# intel-edison-pin-breakout.net
KiCad netlist of a schematic drawn in EAGLE
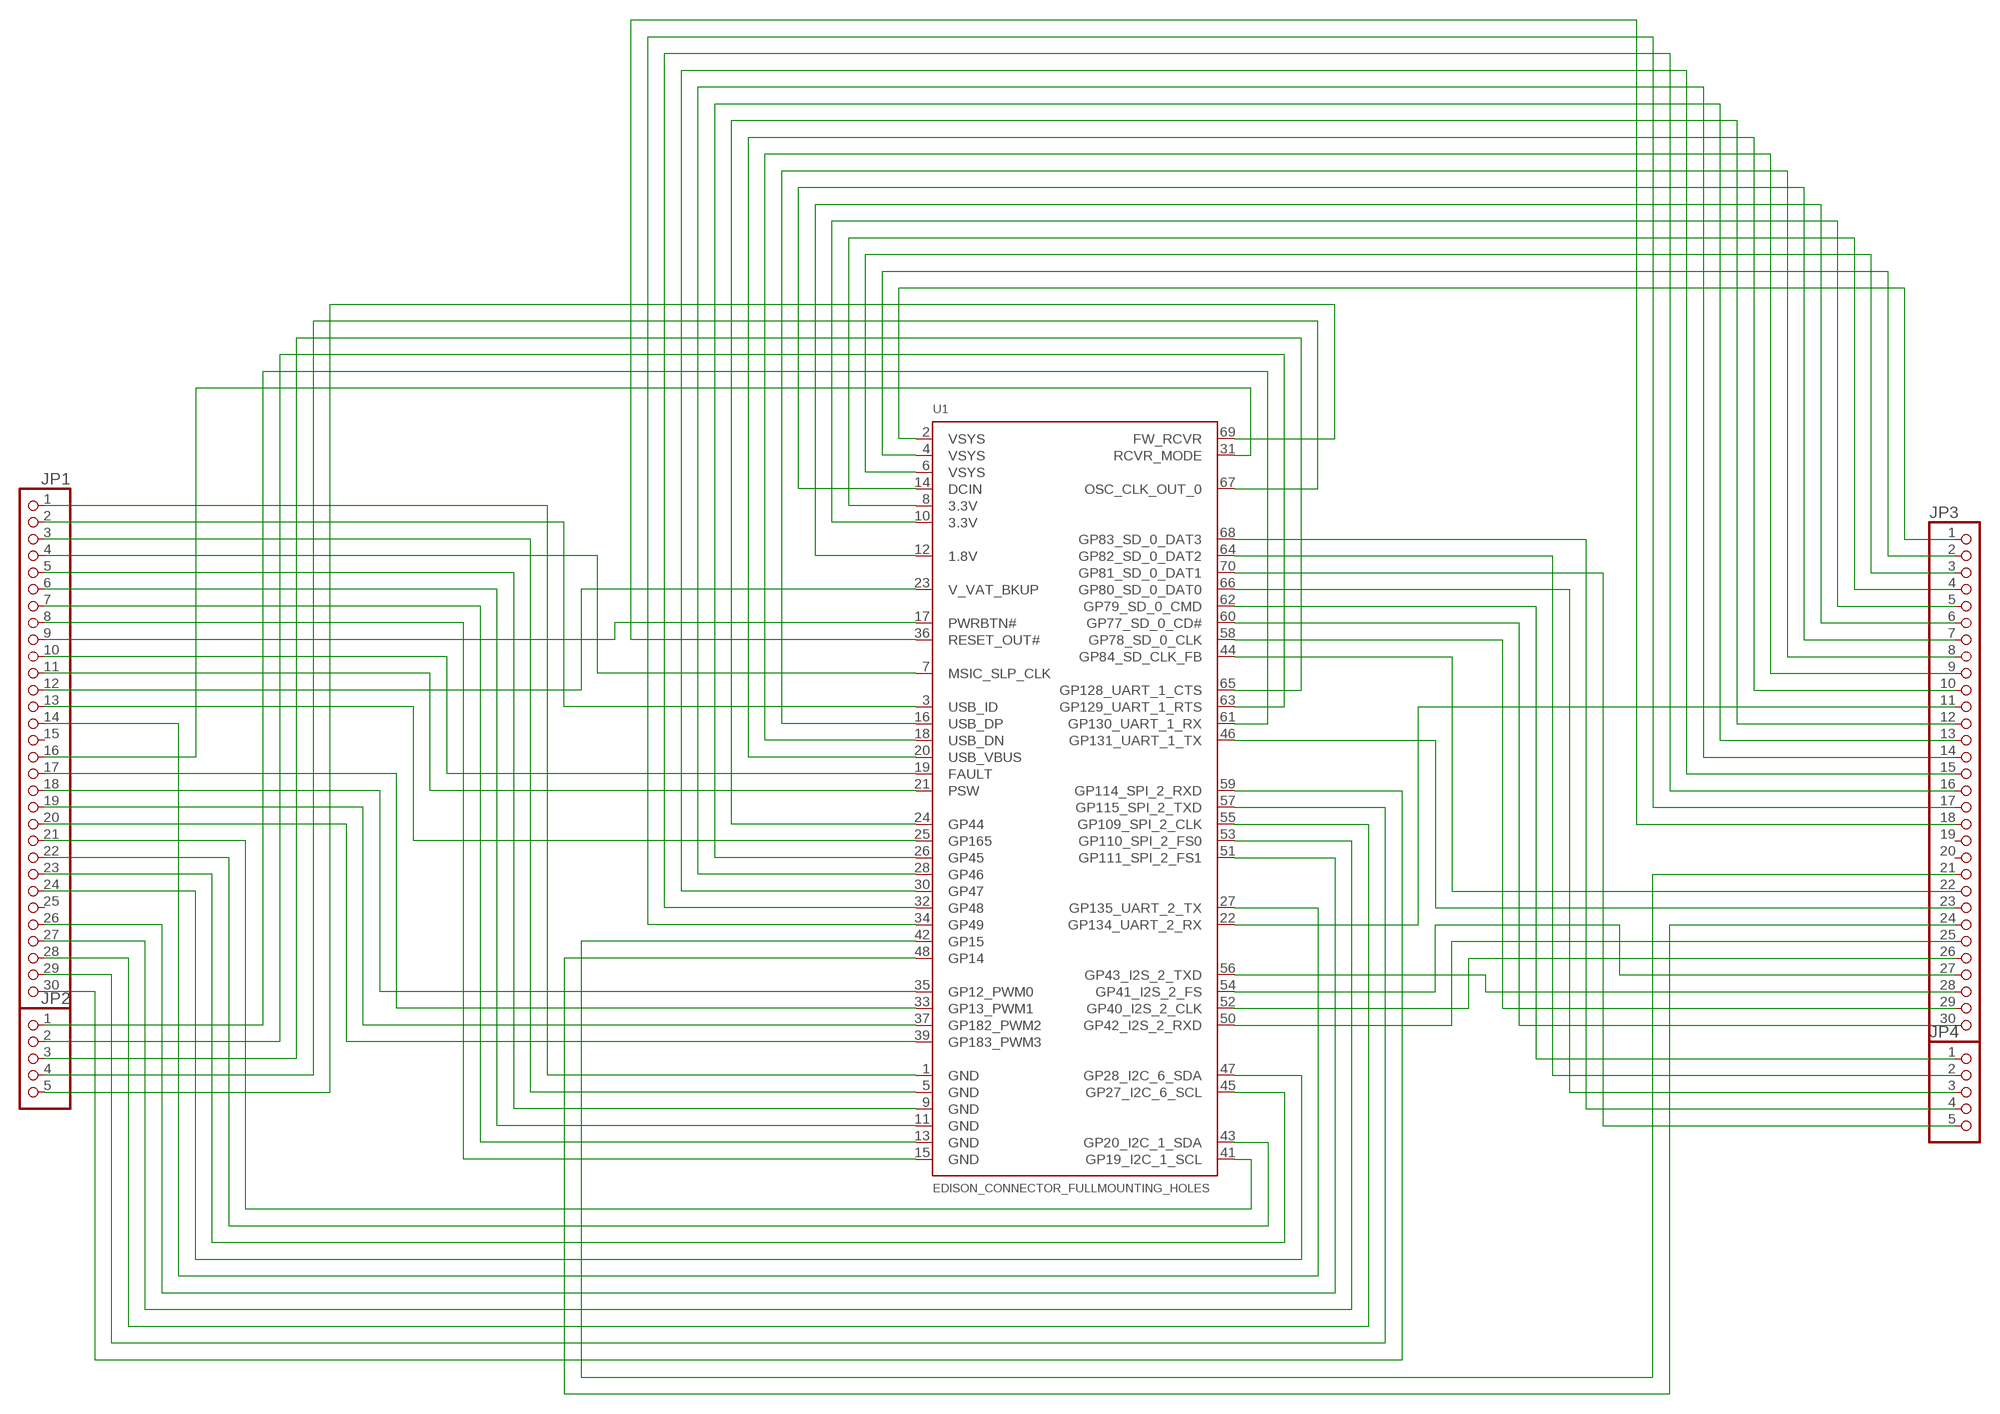
[diagram p0: schematic, sheet 1]

(export (version "E")
  (design (tool "Eeschema 10.0.6"))
  (components
    (comp (ref "JP1")
      (value "PINHD-1X30")
      (footprint "eagle-import:1X30")
      (libsource (lib "eagle-import") (part "PINHD-1X30"))
    )
    (comp (ref "JP2")
      (value "PINHD-1X5")
      (footprint "eagle-import:1X05")
      (libsource (lib "eagle-import") (part "PINHD-1X5"))
    )
    (comp (ref "JP3")
      (value "PINHD-1X30")
      (footprint "eagle-import:1X30")
      (libsource (lib "eagle-import") (part "PINHD-1X30"))
    )
    (comp (ref "JP4")
      (value "PINHD-1X5")
      (footprint "eagle-import:1X05")
      (libsource (lib "eagle-import") (part "PINHD-1X5"))
    )
    (comp (ref "U1")
      (value "EDISON_CONNECTOR_FULLMOUNTING_HOLES")
      (footprint "eagle-import:EDISON_DAUGHTER")
      (libsource (lib "eagle-import") (part "EDISON_CONNECTOR_FULLMOUNTING_HOLES"))
    )
  )
  (nets
    (net (code "1") (name "Net-(JP1-Pad1)") (class "Default")
      (node (ref "JP1") (pin "1") (pinfunction "1_1") (pintype "passive"))
      (node (ref "U1") (pin "1") (pinfunction "GND_1") (pintype "bidirectional"))
    )
    (net (code "2") (name "Net-(JP1-Pad3)") (class "Default")
      (node (ref "JP1") (pin "3") (pinfunction "3_3") (pintype "passive"))
      (node (ref "U1") (pin "5") (pinfunction "GND_5") (pintype "bidirectional"))
    )
    (net (code "3") (name "Net-(JP1-Pad5)") (class "Default")
      (node (ref "JP1") (pin "5") (pinfunction "5_5") (pintype "passive"))
      (node (ref "U1") (pin "9") (pinfunction "GND_9") (pintype "bidirectional"))
    )
    (net (code "4") (name "Net-(JP1-Pad6)") (class "Default")
      (node (ref "JP1") (pin "6") (pinfunction "6_6") (pintype "passive"))
      (node (ref "U1") (pin "11") (pinfunction "GND_11") (pintype "bidirectional"))
    )
    (net (code "5") (name "Net-(JP1-Pad7)") (class "Default")
      (node (ref "JP1") (pin "7") (pinfunction "7_7") (pintype "passive"))
      (node (ref "U1") (pin "13") (pinfunction "GND_13") (pintype "bidirectional"))
    )
    (net (code "6") (name "Net-(JP1-Pad8)") (class "Default")
      (node (ref "JP1") (pin "8") (pinfunction "8_8") (pintype "passive"))
      (node (ref "U1") (pin "15") (pinfunction "GND_15") (pintype "bidirectional"))
    )
    (net (code "7") (name "Net-(JP3-Pad1)") (class "Default")
      (node (ref "JP3") (pin "1") (pinfunction "1_1") (pintype "passive"))
      (node (ref "U1") (pin "2") (pinfunction "VSYS_2") (pintype "bidirectional"))
    )
    (net (code "8") (name "Net-(JP3-Pad2)") (class "Default")
      (node (ref "JP3") (pin "2") (pinfunction "2_2") (pintype "passive"))
      (node (ref "U1") (pin "4") (pinfunction "VSYS_4") (pintype "bidirectional"))
    )
    (net (code "9") (name "Net-(JP3-Pad3)") (class "Default")
      (node (ref "JP3") (pin "3") (pinfunction "3_3") (pintype "passive"))
      (node (ref "U1") (pin "6") (pinfunction "VSYS_6") (pintype "bidirectional"))
    )
    (net (code "10") (name "Net-(JP3-Pad4)") (class "Default")
      (node (ref "JP3") (pin "4") (pinfunction "4_4") (pintype "passive"))
      (node (ref "U1") (pin "8") (pinfunction "3.3V_8") (pintype "bidirectional"))
    )
    (net (code "11") (name "Net-(JP3-Pad5)") (class "Default")
      (node (ref "JP3") (pin "5") (pinfunction "5_5") (pintype "passive"))
      (node (ref "U1") (pin "10") (pinfunction "3.3V_10") (pintype "bidirectional"))
    )
    (net (code "12") (name "Net-(U1-1.8V)") (class "Default")
      (node (ref "JP3") (pin "6") (pinfunction "6_6") (pintype "passive"))
      (node (ref "U1") (pin "12") (pinfunction "1.8V_12") (pintype "bidirectional"))
    )
    (net (code "13") (name "Net-(U1-DCIN)") (class "Default")
      (node (ref "JP3") (pin "7") (pinfunction "7_7") (pintype "passive"))
      (node (ref "U1") (pin "14") (pinfunction "DCIN_14") (pintype "bidirectional"))
    )
    (net (code "14") (name "Net-(U1-FAULT)") (class "Default")
      (node (ref "JP1") (pin "10") (pinfunction "10_10") (pintype "passive"))
      (node (ref "U1") (pin "19") (pinfunction "FAULT_19") (pintype "bidirectional"))
    )
    (net (code "15") (name "Net-(U1-FW_RCVR)") (class "Default")
      (node (ref "JP2") (pin "5") (pinfunction "5_5") (pintype "passive"))
      (node (ref "U1") (pin "69") (pinfunction "FW_RCVR_69") (pintype "bidirectional"))
    )
    (net (code "16") (name "Net-(U1-GP12_PWM0)") (class "Default")
      (node (ref "JP1") (pin "18") (pinfunction "18_18") (pintype "passive"))
      (node (ref "U1") (pin "35") (pinfunction "GP12_PWM0_35") (pintype "bidirectional"))
    )
    (net (code "17") (name "Net-(U1-GP13_PWM1)") (class "Default")
      (node (ref "JP1") (pin "17") (pinfunction "17_17") (pintype "passive"))
      (node (ref "U1") (pin "33") (pinfunction "GP13_PWM1_33") (pintype "bidirectional"))
    )
    (net (code "18") (name "Net-(U1-GP14)") (class "Default")
      (node (ref "JP3") (pin "24") (pinfunction "24_24") (pintype "passive"))
      (node (ref "U1") (pin "48") (pinfunction "GP14_48") (pintype "bidirectional"))
    )
    (net (code "19") (name "Net-(U1-GP15)") (class "Default")
      (node (ref "JP3") (pin "21") (pinfunction "21_21") (pintype "passive"))
      (node (ref "U1") (pin "42") (pinfunction "GP15_42") (pintype "bidirectional"))
    )
    (net (code "20") (name "Net-(U1-GP19_I2C_1_SCL)") (class "Default")
      (node (ref "JP1") (pin "21") (pinfunction "21_21") (pintype "passive"))
      (node (ref "U1") (pin "41") (pinfunction "GP19_I2C_1_SCL_41") (pintype "bidirectional"))
    )
    (net (code "21") (name "Net-(U1-GP20_I2C_1_SDA)") (class "Default")
      (node (ref "JP1") (pin "22") (pinfunction "22_22") (pintype "passive"))
      (node (ref "U1") (pin "43") (pinfunction "GP20_I2C_1_SDA_43") (pintype "bidirectional"))
    )
    (net (code "22") (name "Net-(U1-GP27_I2C_6_SCL)") (class "Default")
      (node (ref "JP1") (pin "23") (pinfunction "23_23") (pintype "passive"))
      (node (ref "U1") (pin "45") (pinfunction "GP27_I2C_6_SCL_45") (pintype "bidirectional"))
    )
    (net (code "23") (name "Net-(U1-GP28_I2C_6_SDA)") (class "Default")
      (node (ref "JP1") (pin "24") (pinfunction "24_24") (pintype "passive"))
      (node (ref "U1") (pin "47") (pinfunction "GP28_I2C_6_SDA_47") (pintype "bidirectional"))
    )
    (net (code "24") (name "Net-(U1-GP40_I2S_2_CLK)") (class "Default")
      (node (ref "JP3") (pin "26") (pinfunction "26_26") (pintype "passive"))
      (node (ref "U1") (pin "52") (pinfunction "GP40_I2S_2_CLK_52") (pintype "bidirectional"))
    )
    (net (code "25") (name "Net-(U1-GP41_I2S_2_FS)") (class "Default")
      (node (ref "JP3") (pin "27") (pinfunction "27_27") (pintype "passive"))
      (node (ref "U1") (pin "54") (pinfunction "GP41_I2S_2_FS_54") (pintype "bidirectional"))
    )
    (net (code "26") (name "Net-(U1-GP42_I2S_2_RXD)") (class "Default")
      (node (ref "JP3") (pin "25") (pinfunction "25_25") (pintype "passive"))
      (node (ref "U1") (pin "50") (pinfunction "GP42_I2S_2_RXD_50") (pintype "bidirectional"))
    )
    (net (code "27") (name "Net-(U1-GP43_I2S_2_TXD)") (class "Default")
      (node (ref "JP3") (pin "28") (pinfunction "28_28") (pintype "passive"))
      (node (ref "U1") (pin "56") (pinfunction "GP43_I2S_2_TXD_56") (pintype "bidirectional"))
    )
    (net (code "28") (name "Net-(U1-GP44)") (class "Default")
      (node (ref "JP3") (pin "12") (pinfunction "12_12") (pintype "passive"))
      (node (ref "U1") (pin "24") (pinfunction "GP44_24") (pintype "bidirectional"))
    )
    (net (code "29") (name "Net-(U1-GP45)") (class "Default")
      (node (ref "JP3") (pin "13") (pinfunction "13_13") (pintype "passive"))
      (node (ref "U1") (pin "26") (pinfunction "GP45_26") (pintype "bidirectional"))
    )
    (net (code "30") (name "Net-(U1-GP46)") (class "Default")
      (node (ref "JP3") (pin "14") (pinfunction "14_14") (pintype "passive"))
      (node (ref "U1") (pin "28") (pinfunction "GP46_28") (pintype "bidirectional"))
    )
    (net (code "31") (name "Net-(U1-GP47)") (class "Default")
      (node (ref "JP3") (pin "15") (pinfunction "15_15") (pintype "passive"))
      (node (ref "U1") (pin "30") (pinfunction "GP47_30") (pintype "bidirectional"))
    )
    (net (code "32") (name "Net-(U1-GP48)") (class "Default")
      (node (ref "JP3") (pin "16") (pinfunction "16_16") (pintype "passive"))
      (node (ref "U1") (pin "32") (pinfunction "GP48_32") (pintype "bidirectional"))
    )
    (net (code "33") (name "Net-(U1-GP49)") (class "Default")
      (node (ref "JP3") (pin "17") (pinfunction "17_17") (pintype "passive"))
      (node (ref "U1") (pin "34") (pinfunction "GP49_34") (pintype "bidirectional"))
    )
    (net (code "34") (name "Net-(U1-GP77_SD_0_CD#)") (class "Default")
      (node (ref "JP3") (pin "30") (pinfunction "30_30") (pintype "passive"))
      (node (ref "U1") (pin "60") (pinfunction "GP77_SD_0_CD#_60") (pintype "bidirectional"))
    )
    (net (code "35") (name "Net-(U1-GP78_SD_0_CLK)") (class "Default")
      (node (ref "JP3") (pin "29") (pinfunction "29_29") (pintype "passive"))
      (node (ref "U1") (pin "58") (pinfunction "GP78_SD_0_CLK_58") (pintype "bidirectional"))
    )
    (net (code "36") (name "Net-(U1-GP79_SD_0_CMD)") (class "Default")
      (node (ref "JP4") (pin "1") (pinfunction "1_1") (pintype "passive"))
      (node (ref "U1") (pin "62") (pinfunction "GP79_SD_0_CMD_62") (pintype "bidirectional"))
    )
    (net (code "37") (name "Net-(U1-GP80_SD_0_DAT0)") (class "Default")
      (node (ref "JP4") (pin "3") (pinfunction "3_3") (pintype "passive"))
      (node (ref "U1") (pin "66") (pinfunction "GP80_SD_0_DAT0_66") (pintype "bidirectional"))
    )
    (net (code "38") (name "Net-(U1-GP81_SD_0_DAT1)") (class "Default")
      (node (ref "JP4") (pin "5") (pinfunction "5_5") (pintype "passive"))
      (node (ref "U1") (pin "70") (pinfunction "GP81_SD_0_DAT1_70") (pintype "bidirectional"))
    )
    (net (code "39") (name "Net-(U1-GP82_SD_0_DAT2)") (class "Default")
      (node (ref "JP4") (pin "2") (pinfunction "2_2") (pintype "passive"))
      (node (ref "U1") (pin "64") (pinfunction "GP82_SD_0_DAT2_64") (pintype "bidirectional"))
    )
    (net (code "40") (name "Net-(U1-GP83_SD_0_DAT3)") (class "Default")
      (node (ref "JP4") (pin "4") (pinfunction "4_4") (pintype "passive"))
      (node (ref "U1") (pin "68") (pinfunction "GP83_SD_0_DAT3_68") (pintype "bidirectional"))
    )
    (net (code "41") (name "Net-(U1-GP84_SD_CLK_FB)") (class "Default")
      (node (ref "JP3") (pin "22") (pinfunction "22_22") (pintype "passive"))
      (node (ref "U1") (pin "44") (pinfunction "GP84_SD_CLK_FB_44") (pintype "bidirectional"))
    )
    (net (code "42") (name "Net-(U1-GP109_SPI_2_CLK)") (class "Default")
      (node (ref "JP1") (pin "28") (pinfunction "28_28") (pintype "passive"))
      (node (ref "U1") (pin "55") (pinfunction "GP109_SPI_2_CLK_55") (pintype "bidirectional"))
    )
    (net (code "43") (name "Net-(U1-GP110_SPI_2_FS0)") (class "Default")
      (node (ref "JP1") (pin "27") (pinfunction "27_27") (pintype "passive"))
      (node (ref "U1") (pin "53") (pinfunction "GP110_SPI_2_FS0_53") (pintype "bidirectional"))
    )
    (net (code "44") (name "Net-(U1-GP111_SPI_2_FS1)") (class "Default")
      (node (ref "JP1") (pin "26") (pinfunction "26_26") (pintype "passive"))
      (node (ref "U1") (pin "51") (pinfunction "GP111_SPI_2_FS1_51") (pintype "bidirectional"))
    )
    (net (code "45") (name "Net-(U1-GP114_SPI_2_RXD)") (class "Default")
      (node (ref "JP1") (pin "30") (pinfunction "30_30") (pintype "passive"))
      (node (ref "U1") (pin "59") (pinfunction "GP114_SPI_2_RXD_59") (pintype "bidirectional"))
    )
    (net (code "46") (name "Net-(U1-GP115_SPI_2_TXD)") (class "Default")
      (node (ref "JP1") (pin "29") (pinfunction "29_29") (pintype "passive"))
      (node (ref "U1") (pin "57") (pinfunction "GP115_SPI_2_TXD_57") (pintype "bidirectional"))
    )
    (net (code "47") (name "Net-(U1-GP128_UART_1_CTS)") (class "Default")
      (node (ref "JP2") (pin "3") (pinfunction "3_3") (pintype "passive"))
      (node (ref "U1") (pin "65") (pinfunction "GP128_UART_1_CTS_65") (pintype "bidirectional"))
    )
    (net (code "48") (name "Net-(U1-GP129_UART_1_RTS)") (class "Default")
      (node (ref "JP2") (pin "2") (pinfunction "2_2") (pintype "passive"))
      (node (ref "U1") (pin "63") (pinfunction "GP129_UART_1_RTS_63") (pintype "bidirectional"))
    )
    (net (code "49") (name "Net-(U1-GP130_UART_1_RX)") (class "Default")
      (node (ref "JP2") (pin "1") (pinfunction "1_1") (pintype "passive"))
      (node (ref "U1") (pin "61") (pinfunction "GP130_UART_1_RX_61") (pintype "bidirectional"))
    )
    (net (code "50") (name "Net-(U1-GP131_UART_1_TX)") (class "Default")
      (node (ref "JP3") (pin "23") (pinfunction "23_23") (pintype "passive"))
      (node (ref "U1") (pin "46") (pinfunction "GP131_UART_1_TX_46") (pintype "bidirectional"))
    )
    (net (code "51") (name "Net-(U1-GP134_UART_2_RX)") (class "Default")
      (node (ref "JP3") (pin "11") (pinfunction "11_11") (pintype "passive"))
      (node (ref "U1") (pin "22") (pinfunction "GP134_UART_2_RX_22") (pintype "bidirectional"))
    )
    (net (code "52") (name "Net-(U1-GP135_UART_2_TX)") (class "Default")
      (node (ref "JP1") (pin "14") (pinfunction "14_14") (pintype "passive"))
      (node (ref "U1") (pin "27") (pinfunction "GP135_UART_2_TX_27") (pintype "bidirectional"))
    )
    (net (code "53") (name "Net-(U1-GP165)") (class "Default")
      (node (ref "JP1") (pin "13") (pinfunction "13_13") (pintype "passive"))
      (node (ref "U1") (pin "25") (pinfunction "GP165_25") (pintype "bidirectional"))
    )
    (net (code "54") (name "Net-(U1-GP182_PWM2)") (class "Default")
      (node (ref "JP1") (pin "19") (pinfunction "19_19") (pintype "passive"))
      (node (ref "U1") (pin "37") (pinfunction "GP182_PWM2_37") (pintype "bidirectional"))
    )
    (net (code "55") (name "Net-(U1-GP183_PWM3)") (class "Default")
      (node (ref "JP1") (pin "20") (pinfunction "20_20") (pintype "passive"))
      (node (ref "U1") (pin "39") (pinfunction "GP183_PWM3_39") (pintype "bidirectional"))
    )
    (net (code "56") (name "Net-(U1-MSIC_SLP_CLK)") (class "Default")
      (node (ref "JP1") (pin "4") (pinfunction "4_4") (pintype "passive"))
      (node (ref "U1") (pin "7") (pinfunction "MSIC_SLP_CLK_7") (pintype "bidirectional"))
    )
    (net (code "57") (name "Net-(U1-OSC_CLK_OUT_0)") (class "Default")
      (node (ref "JP2") (pin "4") (pinfunction "4_4") (pintype "passive"))
      (node (ref "U1") (pin "67") (pinfunction "OSC_CLK_OUT_0_67") (pintype "bidirectional"))
    )
    (net (code "58") (name "Net-(U1-PSW)") (class "Default")
      (node (ref "JP1") (pin "11") (pinfunction "11_11") (pintype "passive"))
      (node (ref "U1") (pin "21") (pinfunction "PSW_21") (pintype "bidirectional"))
    )
    (net (code "59") (name "Net-(U1-PWRBTN#)") (class "Default")
      (node (ref "JP1") (pin "9") (pinfunction "9_9") (pintype "passive"))
      (node (ref "U1") (pin "17") (pinfunction "PWRBTN#_17") (pintype "bidirectional"))
    )
    (net (code "60") (name "Net-(U1-RCVR_MODE)") (class "Default")
      (node (ref "JP1") (pin "16") (pinfunction "16_16") (pintype "passive"))
      (node (ref "U1") (pin "31") (pinfunction "RCVR_MODE_31") (pintype "bidirectional"))
    )
    (net (code "61") (name "Net-(U1-RESET_OUT#)") (class "Default")
      (node (ref "JP3") (pin "18") (pinfunction "18_18") (pintype "passive"))
      (node (ref "U1") (pin "36") (pinfunction "RESET_OUT#_36") (pintype "bidirectional"))
    )
    (net (code "62") (name "Net-(U1-USB_DN)") (class "Default")
      (node (ref "JP3") (pin "9") (pinfunction "9_9") (pintype "passive"))
      (node (ref "U1") (pin "18") (pinfunction "USB_DN_18") (pintype "bidirectional"))
    )
    (net (code "63") (name "Net-(U1-USB_DP)") (class "Default")
      (node (ref "JP3") (pin "8") (pinfunction "8_8") (pintype "passive"))
      (node (ref "U1") (pin "16") (pinfunction "USB_DP_16") (pintype "bidirectional"))
    )
    (net (code "64") (name "Net-(U1-USB_ID)") (class "Default")
      (node (ref "JP1") (pin "2") (pinfunction "2_2") (pintype "passive"))
      (node (ref "U1") (pin "3") (pinfunction "USB_ID_3") (pintype "bidirectional"))
    )
    (net (code "65") (name "Net-(U1-USB_VBUS)") (class "Default")
      (node (ref "JP3") (pin "10") (pinfunction "10_10") (pintype "passive"))
      (node (ref "U1") (pin "20") (pinfunction "USB_VBUS_20") (pintype "bidirectional"))
    )
    (net (code "66") (name "Net-(U1-V_VAT_BKUP)") (class "Default")
      (node (ref "JP1") (pin "12") (pinfunction "12_12") (pintype "passive"))
      (node (ref "U1") (pin "23") (pinfunction "V_VAT_BKUP_23") (pintype "bidirectional"))
    )
    (net (code "67") (name "unconnected-(JP1-Pad15)") (class "Default")
      (node (ref "JP1") (pin "15") (pinfunction "15_15") (pintype "passive"))
    )
    (net (code "68") (name "unconnected-(JP1-Pad25)") (class "Default")
      (node (ref "JP1") (pin "25") (pinfunction "25_25") (pintype "passive"))
    )
    (net (code "69") (name "unconnected-(JP3-Pad19)") (class "Default")
      (node (ref "JP3") (pin "19") (pinfunction "19_19") (pintype "passive"))
    )
    (net (code "70") (name "unconnected-(JP3-Pad20)") (class "Default")
      (node (ref "JP3") (pin "20") (pinfunction "20_20") (pintype "passive"))
    )
  )
)
